# pcb_v2.net
KiCad netlist of a schematic drawn in EAGLE
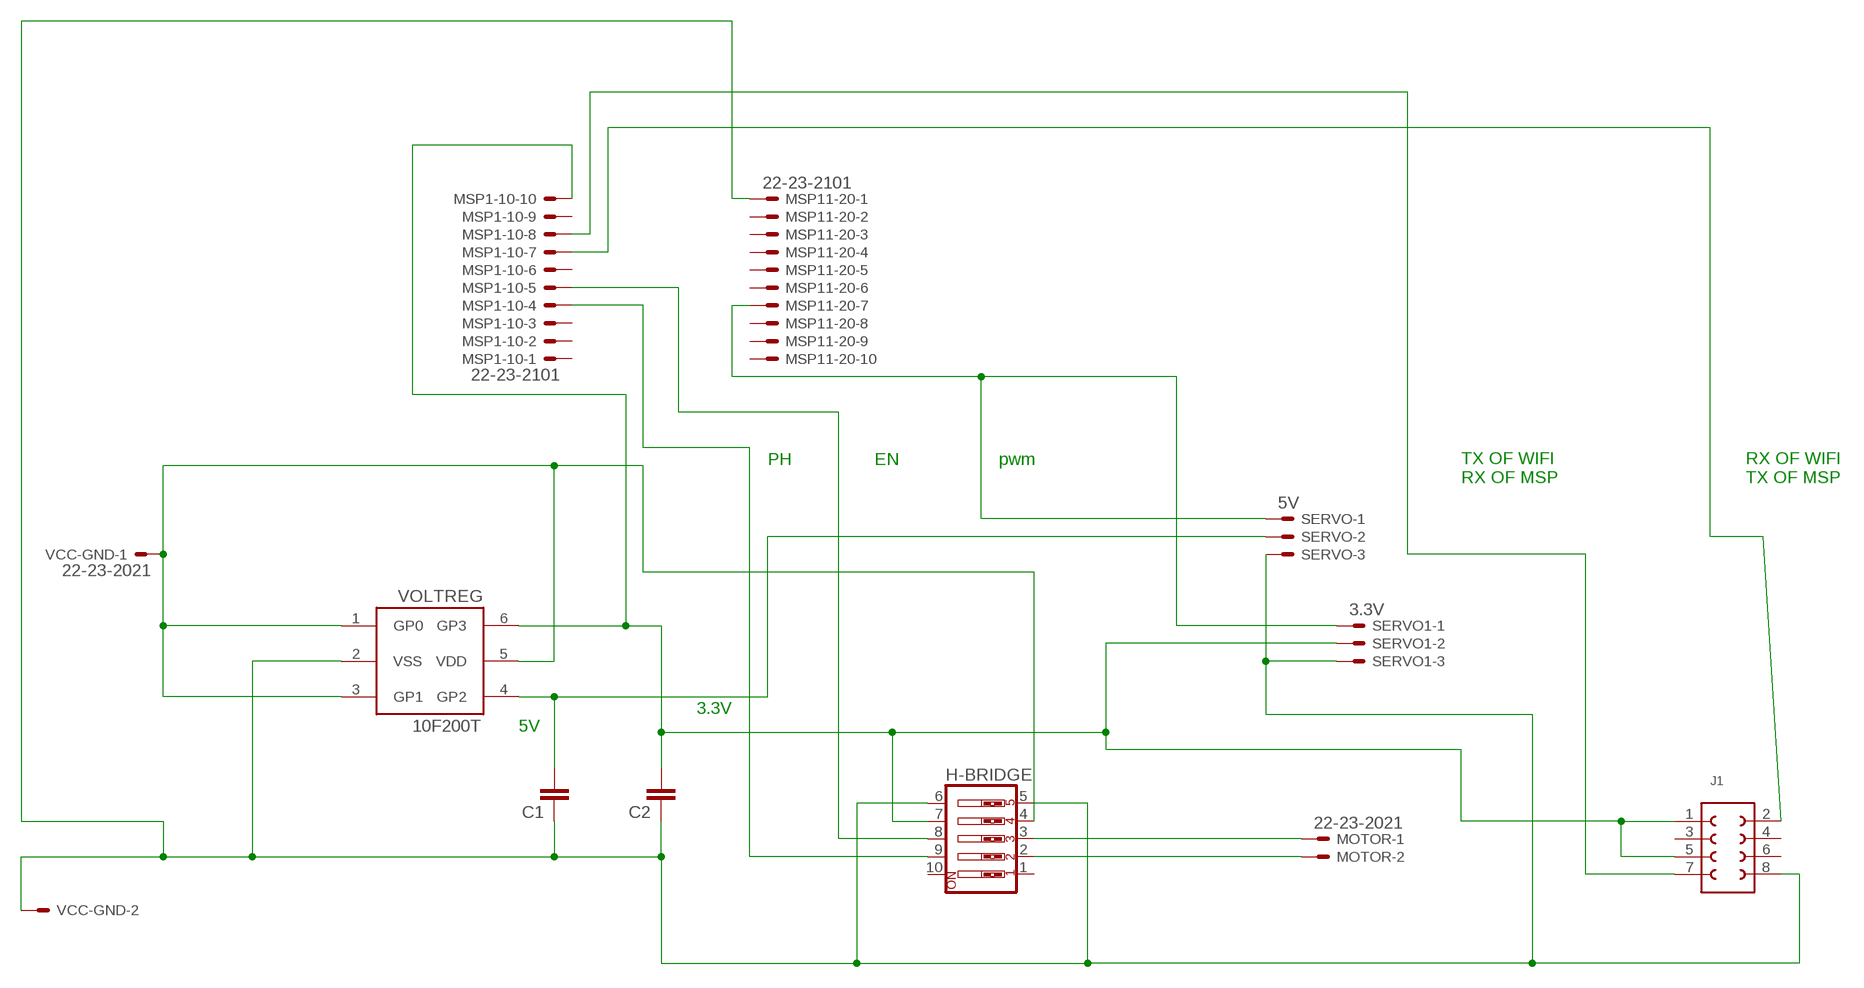
[diagram p0: schematic, sheet 1]

(export (version "E")
  (design (tool "Eeschema 10.0.6"))
  (components
    (comp (ref "C1")
      (value "C2,5-3")
      (footprint "eagle-import:C2.5-3")
      (libsource (lib "eagle-import") (part "C2,5-3"))
    )
    (comp (ref "C2")
      (value "C2,5-3")
      (footprint "eagle-import:C2.5-3")
      (libsource (lib "eagle-import") (part "C2,5-3"))
    )
    (comp (ref "H-BRIDGE")
      (value "SW_DIP-5")
      (footprint "eagle-import:EDG-05")
      (libsource (lib "eagle-import") (part "SW_DIP-5"))
    )
    (comp (ref "J1")
      (value "61300821121")
      (footprint "eagle-import:61300821121")
      (libsource (lib "eagle-import") (part "61300821121"))
    )
    (comp (ref "MOTOR")
      (value "22-23-2021")
      (footprint "eagle-import:22-23-2021")
      (fields (field (name "MF") "MOLEX"))
      (libsource (lib "eagle-import") (part "22-23-2021"))
    )
    (comp (ref "MSP1-10")
      (value "22-23-2101")
      (footprint "eagle-import:22-23-2101")
      (fields (field (name "MF") "MOLEX"))
      (libsource (lib "eagle-import") (part "22-23-2101"))
    )
    (comp (ref "MSP11-20")
      (value "22-23-2101")
      (footprint "eagle-import:22-23-2101")
      (fields (field (name "MF") "MOLEX"))
      (libsource (lib "eagle-import") (part "22-23-2101"))
    )
    (comp (ref "SERVO")
      (value "5V")
      (footprint "eagle-import:22-23-2031")
      (fields (field (name "MF") "MOLEX") (field (name "MPN") "22-23-2031"))
      (libsource (lib "eagle-import") (part "22-23-2031"))
    )
    (comp (ref "SERVO1")
      (value "3.3V")
      (footprint "eagle-import:22-23-2031")
      (fields (field (name "MF") "MOLEX") (field (name "MPN") "22-23-2031"))
      (libsource (lib "eagle-import") (part "22-23-2031"))
    )
    (comp (ref "VCC-GND")
      (value "22-23-2021")
      (footprint "eagle-import:22-23-2021")
      (fields (field (name "MF") "MOLEX"))
      (libsource (lib "eagle-import") (part "22-23-2021"))
    )
    (comp (ref "VOLTREG")
      (value "10F200T")
      (footprint "eagle-import:SOT23-6")
      (libsource (lib "eagle-import") (part "10F200T"))
    )
  )
  (nets
    (net (code "1") (name "Net-(J1-3)") (class "Default")
      (node (ref "C2") (pin "2") (pinfunction "2_2") (pintype "passive"))
      (node (ref "H-BRIDGE") (pin "7") (pinfunction "7_7") (pintype "passive"))
      (node (ref "J1") (pin "1") (pinfunction "1_1") (pintype "passive"))
      (node (ref "J1") (pin "5") (pinfunction "3_5") (pintype "passive"))
      (node (ref "MSP1-10") (pin "10") (pinfunction "S_10") (pintype "passive"))
      (node (ref "SERVO1") (pin "2") (pinfunction "S_2") (pintype "passive"))
      (node (ref "VOLTREG") (pin "6") (pinfunction "GP3_6") (pintype "bidirectional"))
    )
    (net (code "2") (name "Net-(J1-4)") (class "Default")
      (node (ref "J1") (pin "7") (pinfunction "4_7") (pintype "passive"))
      (node (ref "MSP1-10") (pin "8") (pinfunction "S_8") (pintype "passive"))
    )
    (net (code "3") (name "Net-(J1-5)") (class "Default")
      (node (ref "C1") (pin "1") (pinfunction "1_1") (pintype "passive"))
      (node (ref "C2") (pin "1") (pinfunction "1_1") (pintype "passive"))
      (node (ref "H-BRIDGE") (pin "5") (pinfunction "5_5") (pintype "passive"))
      (node (ref "H-BRIDGE") (pin "6") (pinfunction "6_6") (pintype "passive"))
      (node (ref "J1") (pin "8") (pinfunction "5_8") (pintype "passive"))
      (node (ref "MSP11-20") (pin "1") (pinfunction "S_1") (pintype "passive"))
      (node (ref "SERVO") (pin "3") (pinfunction "S_3") (pintype "passive"))
      (node (ref "SERVO1") (pin "3") (pinfunction "S_3") (pintype "passive"))
      (node (ref "VCC-GND") (pin "2") (pinfunction "S_2") (pintype "passive"))
      (node (ref "VOLTREG") (pin "2") (pinfunction "VSS_2") (pintype "power_in"))
    )
    (net (code "4") (name "Net-(J1-8)") (class "Default")
      (node (ref "J1") (pin "2") (pinfunction "8_2") (pintype "passive"))
      (node (ref "MSP1-10") (pin "7") (pinfunction "S_7") (pintype "passive"))
    )
    (net (code "5") (name "Net-(MOTORA-S)") (class "Default")
      (node (ref "H-BRIDGE") (pin "3") (pinfunction "3_3") (pintype "passive"))
      (node (ref "MOTOR") (pin "1") (pinfunction "S_1") (pintype "passive"))
    )
    (net (code "6") (name "Net-(MOTORB-S)") (class "Default")
      (node (ref "H-BRIDGE") (pin "2") (pinfunction "2_2") (pintype "passive"))
      (node (ref "MOTOR") (pin "2") (pinfunction "S_2") (pintype "passive"))
    )
    (net (code "7") (name "Net-(MSP1-10E-S)") (class "Default")
      (node (ref "H-BRIDGE") (pin "9") (pinfunction "9_9") (pintype "passive"))
      (node (ref "MSP1-10") (pin "4") (pinfunction "S_4") (pintype "passive"))
    )
    (net (code "8") (name "Net-(MSP1-10F-S)") (class "Default")
      (node (ref "H-BRIDGE") (pin "8") (pinfunction "8_8") (pintype "passive"))
      (node (ref "MSP1-10") (pin "5") (pinfunction "S_5") (pintype "passive"))
    )
    (net (code "9") (name "Net-(MSP11-20H-S)") (class "Default")
      (node (ref "MSP11-20") (pin "7") (pinfunction "S_7") (pintype "passive"))
      (node (ref "SERVO") (pin "1") (pinfunction "S_1") (pintype "passive"))
      (node (ref "SERVO1") (pin "1") (pinfunction "S_1") (pintype "passive"))
    )
    (net (code "10") (name "Net-(SERVOB-S)") (class "Default")
      (node (ref "C1") (pin "2") (pinfunction "2_2") (pintype "passive"))
      (node (ref "SERVO") (pin "2") (pinfunction "S_2") (pintype "passive"))
      (node (ref "VOLTREG") (pin "4") (pinfunction "GP2_4") (pintype "bidirectional"))
    )
    (net (code "11") (name "Net-(VCC-GNDA-S)") (class "Default")
      (node (ref "H-BRIDGE") (pin "4") (pinfunction "4_4") (pintype "passive"))
      (node (ref "VCC-GND") (pin "1") (pinfunction "S_1") (pintype "passive"))
      (node (ref "VOLTREG") (pin "1") (pinfunction "GP0_1") (pintype "bidirectional"))
      (node (ref "VOLTREG") (pin "3") (pinfunction "GP1_3") (pintype "bidirectional"))
      (node (ref "VOLTREG") (pin "5") (pinfunction "VDD_5") (pintype "power_in"))
    )
    (net (code "12") (name "unconnected-(H-BRIDGE-Pad1)") (class "Default")
      (node (ref "H-BRIDGE") (pin "1") (pinfunction "1_1") (pintype "passive"))
    )
    (net (code "13") (name "unconnected-(H-BRIDGE-Pad10)") (class "Default")
      (node (ref "H-BRIDGE") (pin "10") (pinfunction "10_10") (pintype "passive"))
    )
    (net (code "14") (name "unconnected-(J1-2-Pad3)") (class "Default")
      (node (ref "J1") (pin "3") (pinfunction "2_3") (pintype "passive"))
    )
    (net (code "15") (name "unconnected-(J1-7-Pad4)") (class "Default")
      (node (ref "J1") (pin "4") (pinfunction "7_4") (pintype "passive"))
    )
    (net (code "16") (name "unconnected-(J1-Pad6)") (class "Default")
      (node (ref "J1") (pin "6") (pinfunction "6_6") (pintype "passive"))
    )
    (net (code "17") (name "unconnected-(MSP1-10A-S-Pad1)") (class "Default")
      (node (ref "MSP1-10") (pin "1") (pinfunction "S_1") (pintype "passive"))
    )
    (net (code "18") (name "unconnected-(MSP1-10C-S-Pad2)") (class "Default")
      (node (ref "MSP1-10") (pin "2") (pinfunction "S_2") (pintype "passive"))
    )
    (net (code "19") (name "unconnected-(MSP1-10D-S-Pad3)") (class "Default")
      (node (ref "MSP1-10") (pin "3") (pinfunction "S_3") (pintype "passive"))
    )
    (net (code "20") (name "unconnected-(MSP1-10G-S-Pad6)") (class "Default")
      (node (ref "MSP1-10") (pin "6") (pinfunction "S_6") (pintype "passive"))
    )
    (net (code "21") (name "unconnected-(MSP1-10J-S-Pad9)") (class "Default")
      (node (ref "MSP1-10") (pin "9") (pinfunction "S_9") (pintype "passive"))
    )
    (net (code "22") (name "unconnected-(MSP11-20B-S-Pad10)") (class "Default")
      (node (ref "MSP11-20") (pin "10") (pinfunction "S_10") (pintype "passive"))
    )
    (net (code "23") (name "unconnected-(MSP11-20C-S-Pad2)") (class "Default")
      (node (ref "MSP11-20") (pin "2") (pinfunction "S_2") (pintype "passive"))
    )
    (net (code "24") (name "unconnected-(MSP11-20D-S-Pad3)") (class "Default")
      (node (ref "MSP11-20") (pin "3") (pinfunction "S_3") (pintype "passive"))
    )
    (net (code "25") (name "unconnected-(MSP11-20E-S-Pad4)") (class "Default")
      (node (ref "MSP11-20") (pin "4") (pinfunction "S_4") (pintype "passive"))
    )
    (net (code "26") (name "unconnected-(MSP11-20F-S-Pad5)") (class "Default")
      (node (ref "MSP11-20") (pin "5") (pinfunction "S_5") (pintype "passive"))
    )
    (net (code "27") (name "unconnected-(MSP11-20G-S-Pad6)") (class "Default")
      (node (ref "MSP11-20") (pin "6") (pinfunction "S_6") (pintype "passive"))
    )
    (net (code "28") (name "unconnected-(MSP11-20I-S-Pad8)") (class "Default")
      (node (ref "MSP11-20") (pin "8") (pinfunction "S_8") (pintype "passive"))
    )
    (net (code "29") (name "unconnected-(MSP11-20J-S-Pad9)") (class "Default")
      (node (ref "MSP11-20") (pin "9") (pinfunction "S_9") (pintype "passive"))
    )
  )
)
